# AFE.net
KiCad netlist of a schematic drawn in Altium Designer
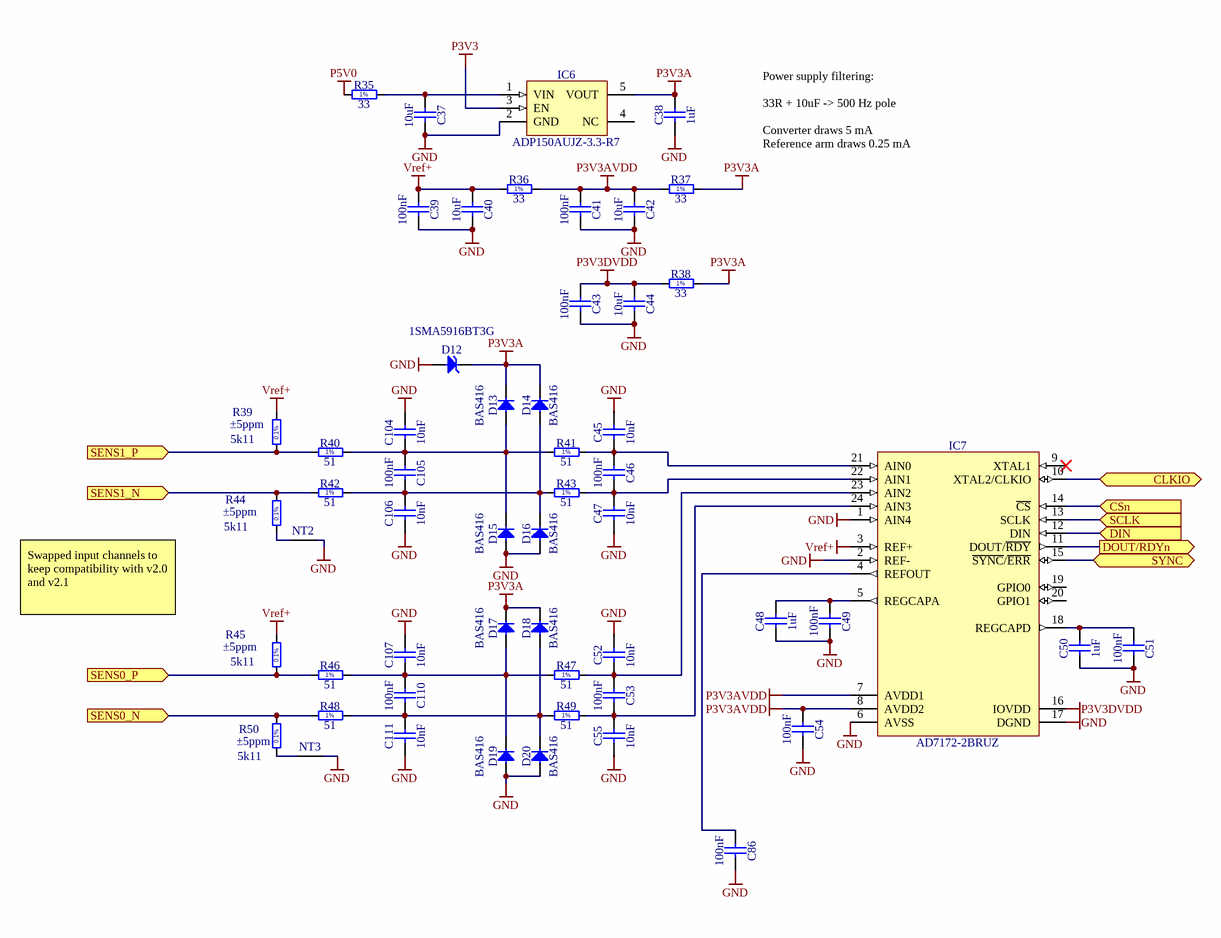
[diagram p0: AFE.SchDoc]

(export (version "E")
  (design (tool "Eeschema 10.0.6"))
  (components
    (comp (ref "C37")
      (value "10uF")
      (footprint "CAPC2012X135N")
      (description "Non-polarised capacitor")
      (fields
        (field (name "PART NUMBER") "CC0805_10UF_16V_10%_X5R")
        (field (name "VOLTAGE") "16V")
        (field (name "AUTHOR") "CERN DEM JLC")
      )
      (libsource (lib "Capacitors") (part "Capacitor - non polarized"))
    )
    (comp (ref "C38")
      (value "1uF")
      (footprint "CAPC1608X87N")
      (description "Non-polarised capacitor")
      (fields
        (field (name "PART NUMBER") "CC0603_1UF_25V_10%_X7R")
        (field (name "VOLTAGE") "25V")
        (field (name "AUTHOR") "CERN DEM JLC")
      )
      (libsource (lib "Capacitors") (part "Capacitor - non polarized"))
    )
    (comp (ref "C39")
      (value "100nF")
      (footprint "CAPC1005X55N")
      (description "Non-polarised capacitor")
      (fields
        (field (name "PART NUMBER") "CC0402_100NF_16V_10%_X5R")
        (field (name "VOLTAGE") "16V")
        (field (name "AUTHOR") "CERN DEM JLC")
      )
      (libsource (lib "Capacitors") (part "Capacitor - non polarized"))
    )
    (comp (ref "C40")
      (value "10uF")
      (footprint "CAPC2012X135N")
      (description "Non-polarised capacitor")
      (fields
        (field (name "PART NUMBER") "CC0805_10UF_16V_10%_X5R")
        (field (name "VOLTAGE") "16V")
        (field (name "AUTHOR") "CERN DEM JLC")
      )
      (libsource (lib "Capacitors") (part "Capacitor - non polarized"))
    )
    (comp (ref "C41")
      (value "100nF")
      (footprint "CAPC1005X55N")
      (description "Non-polarised capacitor")
      (fields
        (field (name "PART NUMBER") "CC0402_100NF_16V_10%_X5R")
        (field (name "VOLTAGE") "16V")
        (field (name "AUTHOR") "CERN DEM JLC")
      )
      (libsource (lib "Capacitors") (part "Capacitor - non polarized"))
    )
    (comp (ref "C42")
      (value "10uF")
      (footprint "CAPC2012X135N")
      (description "Non-polarised capacitor")
      (fields
        (field (name "PART NUMBER") "CC0805_10UF_16V_10%_X5R")
        (field (name "VOLTAGE") "16V")
        (field (name "AUTHOR") "CERN DEM JLC")
      )
      (libsource (lib "Capacitors") (part "Capacitor - non polarized"))
    )
    (comp (ref "C43")
      (value "100nF")
      (footprint "CAPC1005X55N")
      (description "Non-polarised capacitor")
      (fields
        (field (name "PART NUMBER") "CC0402_100NF_16V_10%_X5R")
        (field (name "VOLTAGE") "16V")
        (field (name "AUTHOR") "CERN DEM JLC")
      )
      (libsource (lib "Capacitors") (part "Capacitor - non polarized"))
    )
    (comp (ref "C44")
      (value "10uF")
      (footprint "CAPC2012X135N")
      (description "Non-polarised capacitor")
      (fields
        (field (name "PART NUMBER") "CC0805_10UF_16V_10%_X5R")
        (field (name "VOLTAGE") "16V")
        (field (name "AUTHOR") "CERN DEM JLC")
      )
      (libsource (lib "Capacitors") (part "Capacitor - non polarized"))
    )
    (comp (ref "C45")
      (value "10nF")
      (footprint "CAPC1005X55N")
      (description "Non-polarised capacitor")
      (fields
        (field (name "PART NUMBER") "CC0402_10NF_50V_10%_X7R")
        (field (name "VOLTAGE") "50V")
        (field (name "AUTHOR") "CERN DEM MR")
      )
      (libsource (lib "Capacitors") (part "Capacitor - non polarized"))
    )
    (comp (ref "C46")
      (value "100nF")
      (footprint "CAPC1005X55N")
      (description "Non-polarised capacitor")
      (fields
        (field (name "PART NUMBER") "CC0402_100NF_16V_10%_X5R")
        (field (name "VOLTAGE") "16V")
        (field (name "AUTHOR") "CERN DEM JLC")
      )
      (libsource (lib "Capacitors") (part "Capacitor - non polarized"))
    )
    (comp (ref "C47")
      (value "10nF")
      (footprint "CAPC1005X55N")
      (description "Non-polarised capacitor")
      (fields
        (field (name "PART NUMBER") "CC0402_10NF_50V_10%_X7R")
        (field (name "VOLTAGE") "50V")
        (field (name "AUTHOR") "CERN DEM MR")
      )
      (libsource (lib "Capacitors") (part "Capacitor - non polarized"))
    )
    (comp (ref "C48")
      (value "1uF")
      (footprint "CAPC1608X87N")
      (description "Non-polarised capacitor")
      (fields
        (field (name "PART NUMBER") "CC0603_1UF_25V_10%_X7R")
        (field (name "VOLTAGE") "25V")
        (field (name "AUTHOR") "CERN DEM JLC")
      )
      (libsource (lib "Capacitors") (part "Capacitor - non polarized"))
    )
    (comp (ref "C49")
      (value "100nF")
      (footprint "CAPC1005X55N")
      (description "Non-polarised capacitor")
      (fields
        (field (name "PART NUMBER") "CC0402_100NF_16V_10%_X5R")
        (field (name "VOLTAGE") "16V")
        (field (name "AUTHOR") "CERN DEM JLC")
      )
      (libsource (lib "Capacitors") (part "Capacitor - non polarized"))
    )
    (comp (ref "C50")
      (value "1uF")
      (footprint "CAPC1608X87N")
      (description "Non-polarised capacitor")
      (fields
        (field (name "PART NUMBER") "CC0603_1UF_25V_10%_X7R")
        (field (name "VOLTAGE") "25V")
        (field (name "AUTHOR") "CERN DEM JLC")
      )
      (libsource (lib "Capacitors") (part "Capacitor - non polarized"))
    )
    (comp (ref "C51")
      (value "100nF")
      (footprint "CAPC1005X55N")
      (description "Non-polarised capacitor")
      (fields
        (field (name "PART NUMBER") "CC0402_100NF_16V_10%_X5R")
        (field (name "VOLTAGE") "16V")
        (field (name "AUTHOR") "CERN DEM JLC")
      )
      (libsource (lib "Capacitors") (part "Capacitor - non polarized"))
    )
    (comp (ref "C52")
      (value "10nF")
      (footprint "CAPC1005X55N")
      (description "Non-polarised capacitor")
      (fields
        (field (name "PART NUMBER") "CC0402_10NF_50V_10%_X7R")
        (field (name "VOLTAGE") "50V")
        (field (name "AUTHOR") "CERN DEM MR")
      )
      (libsource (lib "Capacitors") (part "Capacitor - non polarized"))
    )
    (comp (ref "C53")
      (value "100nF")
      (footprint "CAPC1005X55N")
      (description "Non-polarised capacitor")
      (fields
        (field (name "PART NUMBER") "CC0402_100NF_16V_10%_X5R")
        (field (name "VOLTAGE") "16V")
        (field (name "AUTHOR") "CERN DEM JLC")
      )
      (libsource (lib "Capacitors") (part "Capacitor - non polarized"))
    )
    (comp (ref "C54")
      (value "100nF")
      (footprint "CAPC1005X55N")
      (description "Non-polarised capacitor")
      (fields
        (field (name "PART NUMBER") "CC0402_100NF_16V_10%_X5R")
        (field (name "VOLTAGE") "16V")
        (field (name "AUTHOR") "CERN DEM JLC")
      )
      (libsource (lib "Capacitors") (part "Capacitor - non polarized"))
    )
    (comp (ref "C55")
      (value "10nF")
      (footprint "CAPC1005X55N")
      (description "Non-polarised capacitor")
      (fields
        (field (name "PART NUMBER") "CC0402_10NF_50V_10%_X7R")
        (field (name "VOLTAGE") "50V")
        (field (name "AUTHOR") "CERN DEM MR")
      )
      (libsource (lib "Capacitors") (part "Capacitor - non polarized"))
    )
    (comp (ref "C86")
      (value "100nF")
      (footprint "CAPC1005X55N")
      (description "Non-polarised capacitor")
      (fields
        (field (name "PART NUMBER") "CC0402_100NF_16V_10%_X5R")
        (field (name "VOLTAGE") "16V")
        (field (name "AUTHOR") "CERN DEM JLC")
      )
      (libsource (lib "Capacitors") (part "Capacitor - non polarized"))
    )
    (comp (ref "C104")
      (value "10nF")
      (footprint "CAPC1005X55N")
      (description "Non-polarised capacitor")
      (fields
        (field (name "PART NUMBER") "CC0402_10NF_50V_10%_X7R")
        (field (name "VOLTAGE") "50V")
        (field (name "AUTHOR") "CERN DEM MR")
      )
      (libsource (lib "Capacitors") (part "Capacitor - non polarized"))
    )
    (comp (ref "C105")
      (value "100nF")
      (footprint "CAPC1005X55N")
      (description "Non-polarised capacitor")
      (fields
        (field (name "PART NUMBER") "CC0402_100NF_16V_10%_X5R")
        (field (name "VOLTAGE") "16V")
        (field (name "AUTHOR") "CERN DEM JLC")
      )
      (libsource (lib "Capacitors") (part "Capacitor - non polarized"))
    )
    (comp (ref "C106")
      (value "10nF")
      (footprint "CAPC1005X55N")
      (description "Non-polarised capacitor")
      (fields
        (field (name "PART NUMBER") "CC0402_10NF_50V_10%_X7R")
        (field (name "VOLTAGE") "50V")
        (field (name "AUTHOR") "CERN DEM MR")
      )
      (libsource (lib "Capacitors") (part "Capacitor - non polarized"))
    )
    (comp (ref "C107")
      (value "10nF")
      (footprint "CAPC1005X55N")
      (description "Non-polarised capacitor")
      (fields
        (field (name "PART NUMBER") "CC0402_10NF_50V_10%_X7R")
        (field (name "VOLTAGE") "50V")
        (field (name "AUTHOR") "CERN DEM MR")
      )
      (libsource (lib "Capacitors") (part "Capacitor - non polarized"))
    )
    (comp (ref "C110")
      (value "100nF")
      (footprint "CAPC1005X55N")
      (description "Non-polarised capacitor")
      (fields
        (field (name "PART NUMBER") "CC0402_100NF_16V_10%_X5R")
        (field (name "VOLTAGE") "16V")
        (field (name "AUTHOR") "CERN DEM JLC")
      )
      (libsource (lib "Capacitors") (part "Capacitor - non polarized"))
    )
    (comp (ref "C111")
      (value "10nF")
      (footprint "CAPC1005X55N")
      (description "Non-polarised capacitor")
      (fields
        (field (name "PART NUMBER") "CC0402_10NF_50V_10%_X7R")
        (field (name "VOLTAGE") "50V")
        (field (name "AUTHOR") "CERN DEM MR")
      )
      (libsource (lib "Capacitors") (part "Capacitor - non polarized"))
    )
    (comp (ref "D12")
      (value "1SMA5916BT3G")
      (footprint "DIOM5226X220N")
      (description "4.3V 1.5 Watt Plastic Surface Mount Zener Voltage Regulators")
      (fields (field (name "VOLTAGE") "4.3V") (field (name "POWER") "1.5W") (field (name "AUTHOR") "GK"))
      (libsource (lib "Diodes") (part "D_Zener_1SMA5916BT3G"))
    )
    (comp (ref "D13")
      (value "BAS416")
      (footprint "SOD2512X110N")
      (description "Diode")
      (fields
        (field (name "VOLTAGE") "75V")
        (field (name "POWER") "200mA")
        (field (name "AUTHOR") "CERN DEM JLC")
      )
      (libsource (lib "ICs And Semiconductors") (part "Diode"))
    )
    (comp (ref "D14")
      (value "BAS416")
      (footprint "SOD2512X110N")
      (description "Diode")
      (fields
        (field (name "VOLTAGE") "75V")
        (field (name "POWER") "200mA")
        (field (name "AUTHOR") "CERN DEM JLC")
      )
      (libsource (lib "ICs And Semiconductors") (part "Diode"))
    )
    (comp (ref "D15")
      (value "BAS416")
      (footprint "SOD2512X110N")
      (description "Diode")
      (fields
        (field (name "VOLTAGE") "75V")
        (field (name "POWER") "200mA")
        (field (name "AUTHOR") "CERN DEM JLC")
      )
      (libsource (lib "ICs And Semiconductors") (part "Diode"))
    )
    (comp (ref "D16")
      (value "BAS416")
      (footprint "SOD2512X110N")
      (description "Diode")
      (fields
        (field (name "VOLTAGE") "75V")
        (field (name "POWER") "200mA")
        (field (name "AUTHOR") "CERN DEM JLC")
      )
      (libsource (lib "ICs And Semiconductors") (part "Diode"))
    )
    (comp (ref "D17")
      (value "BAS416")
      (footprint "SOD2512X110N")
      (description "Diode")
      (fields
        (field (name "VOLTAGE") "75V")
        (field (name "POWER") "200mA")
        (field (name "AUTHOR") "CERN DEM JLC")
      )
      (libsource (lib "ICs And Semiconductors") (part "Diode"))
    )
    (comp (ref "D18")
      (value "BAS416")
      (footprint "SOD2512X110N")
      (description "Diode")
      (fields
        (field (name "VOLTAGE") "75V")
        (field (name "POWER") "200mA")
        (field (name "AUTHOR") "CERN DEM JLC")
      )
      (libsource (lib "ICs And Semiconductors") (part "Diode"))
    )
    (comp (ref "D19")
      (value "BAS416")
      (footprint "SOD2512X110N")
      (description "Diode")
      (fields
        (field (name "VOLTAGE") "75V")
        (field (name "POWER") "200mA")
        (field (name "AUTHOR") "CERN DEM JLC")
      )
      (libsource (lib "ICs And Semiconductors") (part "Diode"))
    )
    (comp (ref "D20")
      (value "BAS416")
      (footprint "SOD2512X110N")
      (description "Diode")
      (fields
        (field (name "VOLTAGE") "75V")
        (field (name "POWER") "200mA")
        (field (name "AUTHOR") "CERN DEM JLC")
      )
      (libsource (lib "ICs And Semiconductors") (part "Diode"))
    )
    (comp (ref "IC6")
      (value "ADP150AUJZ-3.3-R7")
      (footprint "SOT95P280X90-5N")
      (description "Ultralow Noise, 150 mA CMOS Linear Regulator")
      (fields (field (name "MANUFACTURER") "ANALOG DEVICES") (field (name "AUTHOR") "CERN DEM JLC"))
      (libsource (lib "ICs And Semiconductors") (part "ADP150AUJZ"))
    )
    (comp (ref "IC7")
      (value "AD7172-2BRUZ")
      (footprint "SOP65P640X120-24N")
      (description "32-Bit, 10 kSPS, Sigma-Delta ADC with 100 µs Settling and True Rail-to-Rail Buffers")
      (fields (field (name "MANUFACTURER") "ANALOG DEVICES") (field (name "AUTHOR") "GK"))
      (libsource (lib "LIBRARY_SCH") (part "ADC_AD7172-2"))
    )
    (comp (ref "NT2")
      (value "Net Tie")
      (footprint "Net Tie")
      (fields (field (name "AUTHOR") "CERN DEM JLC"))
      (libsource (lib "Eletro-mechanical") (part "Net Tie"))
    )
    (comp (ref "NT3")
      (value "Net Tie")
      (footprint "Net Tie")
      (fields (field (name "AUTHOR") "CERN DEM JLC"))
      (libsource (lib "Eletro-mechanical") (part "Net Tie"))
    )
    (comp (ref "R35")
      (value "33")
      (footprint "RESC1005X40N")
      (description "Resistor - 1%")
      (fields
        (field (name "PART NUMBER") "R0402_33R_1%_0.0625W_100PPM")
        (field (name "POWER") "0.0625W")
        (field (name "AUTHOR") "CERN DEM JLC")
      )
      (libsource (lib "Resistors") (part "Resistor - 1%"))
    )
    (comp (ref "R36")
      (value "33")
      (footprint "RESC1005X40N")
      (description "Resistor - 1%")
      (fields
        (field (name "PART NUMBER") "R0402_33R_1%_0.0625W_100PPM")
        (field (name "POWER") "0.0625W")
        (field (name "AUTHOR") "CERN DEM JLC")
      )
      (libsource (lib "Resistors") (part "Resistor - 1%"))
    )
    (comp (ref "R37")
      (value "33")
      (footprint "RESC1005X40N")
      (description "Resistor - 1%")
      (fields
        (field (name "PART NUMBER") "R0402_33R_1%_0.0625W_100PPM")
        (field (name "POWER") "0.0625W")
        (field (name "AUTHOR") "CERN DEM JLC")
      )
      (libsource (lib "Resistors") (part "Resistor - 1%"))
    )
    (comp (ref "R38")
      (value "33")
      (footprint "RESC1005X40N")
      (description "Resistor - 1%")
      (fields
        (field (name "PART NUMBER") "R0402_33R_1%_0.0625W_100PPM")
        (field (name "POWER") "0.0625W")
        (field (name "AUTHOR") "CERN DEM JLC")
      )
      (libsource (lib "Resistors") (part "Resistor - 1%"))
    )
    (comp (ref "R39")
      (value "5k11")
      (footprint "RESC1608X55N")
      (description "Resistor - 0.1%")
      (fields
        (field (name "PART NUMBER") "R0603_5K11_0.1%_0.063W_5PPM")
        (field (name "POWER") "0.063W")
        (field (name "TC") "±5ppm")
        (field (name "AUTHOR") "GK")
      )
      (libsource (lib "LIBRARY_SCH") (part "RES_0603_5k11_0.1%_5ppm"))
    )
    (comp (ref "R40")
      (value "51")
      (footprint "RESC1005X40N")
      (description "Resistor - 1%")
      (fields
        (field (name "PART NUMBER") "R0402_51R_1%_0.0625W_100PPM")
        (field (name "POWER") "0.0625W")
        (field (name "AUTHOR") "CERN DEM JLC")
      )
      (libsource (lib "Resistors") (part "Resistor - 1%"))
    )
    (comp (ref "R41")
      (value "51")
      (footprint "RESC1005X40N")
      (description "Resistor - 1%")
      (fields
        (field (name "PART NUMBER") "R0402_51R_1%_0.0625W_100PPM")
        (field (name "POWER") "0.0625W")
        (field (name "AUTHOR") "CERN DEM JLC")
      )
      (libsource (lib "Resistors") (part "Resistor - 1%"))
    )
    (comp (ref "R42")
      (value "51")
      (footprint "RESC1005X40N")
      (description "Resistor - 1%")
      (fields
        (field (name "PART NUMBER") "R0402_51R_1%_0.0625W_100PPM")
        (field (name "POWER") "0.0625W")
        (field (name "AUTHOR") "CERN DEM JLC")
      )
      (libsource (lib "Resistors") (part "Resistor - 1%"))
    )
    (comp (ref "R43")
      (value "51")
      (footprint "RESC1005X40N")
      (description "Resistor - 1%")
      (fields
        (field (name "PART NUMBER") "R0402_51R_1%_0.0625W_100PPM")
        (field (name "POWER") "0.0625W")
        (field (name "AUTHOR") "CERN DEM JLC")
      )
      (libsource (lib "Resistors") (part "Resistor - 1%"))
    )
    (comp (ref "R44")
      (value "5k11")
      (footprint "RESC1608X55N")
      (description "Resistor - 0.1%")
      (fields
        (field (name "PART NUMBER") "R0603_5K11_0.1%_0.063W_5PPM")
        (field (name "POWER") "0.063W")
        (field (name "TC") "±5ppm")
        (field (name "AUTHOR") "GK")
      )
      (libsource (lib "LIBRARY_SCH") (part "RES_0603_5k11_0.1%_5ppm"))
    )
    (comp (ref "R45")
      (value "5k11")
      (footprint "RESC1608X55N")
      (description "Resistor - 0.1%")
      (fields
        (field (name "PART NUMBER") "R0603_5K11_0.1%_0.063W_5PPM")
        (field (name "POWER") "0.063W")
        (field (name "TC") "±5ppm")
        (field (name "AUTHOR") "GK")
      )
      (libsource (lib "LIBRARY_SCH") (part "RES_0603_5k11_0.1%_5ppm"))
    )
    (comp (ref "R46")
      (value "51")
      (footprint "RESC1005X40N")
      (description "Resistor - 1%")
      (fields
        (field (name "PART NUMBER") "R0402_51R_1%_0.0625W_100PPM")
        (field (name "POWER") "0.0625W")
        (field (name "AUTHOR") "CERN DEM JLC")
      )
      (libsource (lib "Resistors") (part "Resistor - 1%"))
    )
    (comp (ref "R47")
      (value "51")
      (footprint "RESC1005X40N")
      (description "Resistor - 1%")
      (fields
        (field (name "PART NUMBER") "R0402_51R_1%_0.0625W_100PPM")
        (field (name "POWER") "0.0625W")
        (field (name "AUTHOR") "CERN DEM JLC")
      )
      (libsource (lib "Resistors") (part "Resistor - 1%"))
    )
    (comp (ref "R48")
      (value "51")
      (footprint "RESC1005X40N")
      (description "Resistor - 1%")
      (fields
        (field (name "PART NUMBER") "R0402_51R_1%_0.0625W_100PPM")
        (field (name "POWER") "0.0625W")
        (field (name "AUTHOR") "CERN DEM JLC")
      )
      (libsource (lib "Resistors") (part "Resistor - 1%"))
    )
    (comp (ref "R49")
      (value "51")
      (footprint "RESC1005X40N")
      (description "Resistor - 1%")
      (fields
        (field (name "PART NUMBER") "R0402_51R_1%_0.0625W_100PPM")
        (field (name "POWER") "0.0625W")
        (field (name "AUTHOR") "CERN DEM JLC")
      )
      (libsource (lib "Resistors") (part "Resistor - 1%"))
    )
    (comp (ref "R50")
      (value "5k11")
      (footprint "RESC1608X55N")
      (description "Resistor - 0.1%")
      (fields
        (field (name "PART NUMBER") "R0603_5K11_0.1%_0.063W_5PPM")
        (field (name "POWER") "0.063W")
        (field (name "TC") "±5ppm")
        (field (name "AUTHOR") "GK")
      )
      (libsource (lib "LIBRARY_SCH") (part "RES_0603_5k11_0.1%_5ppm"))
    )
  )
  (nets
    (net (code "1") (name "/CLKIO") (class "Default")
      (node (ref "IC7") (pin "10") (pinfunction "XTAL2/CLKIO_10") (pintype "bidirectional"))
    )
    (net (code "2") (name "/CSn") (class "Default")
      (node (ref "IC7") (pin "14") (pinfunction "~{CS}_14") (pintype "input"))
    )
    (net (code "3") (name "/DIN") (class "Default")
      (node (ref "IC7") (pin "12") (pinfunction "DIN_12") (pintype "input"))
    )
    (net (code "4") (name "/DOUT{slash}RDYn") (class "Default")
      (node (ref "IC7") (pin "11") (pinfunction "DOUT/~{RDY}_11") (pintype "output"))
    )
    (net (code "5") (name "/SCLK") (class "Default")
      (node (ref "IC7") (pin "13") (pinfunction "SCLK_13") (pintype "input"))
    )
    (net (code "6") (name "/SENS0_N") (class "Default")
      (node (ref "R48") (pin "1") (pinfunction "1_1") (pintype "passive"))
      (node (ref "R50") (pin "2") (pinfunction "2_2") (pintype "passive"))
    )
    (net (code "7") (name "/SENS0_P") (class "Default")
      (node (ref "R45") (pin "1") (pinfunction "1_1") (pintype "passive"))
      (node (ref "R46") (pin "1") (pinfunction "1_1") (pintype "passive"))
    )
    (net (code "8") (name "/SENS1_N") (class "Default")
      (node (ref "R42") (pin "1") (pinfunction "1_1") (pintype "passive"))
      (node (ref "R44") (pin "2") (pinfunction "2_2") (pintype "passive"))
    )
    (net (code "9") (name "/SENS1_P") (class "Default")
      (node (ref "R39") (pin "1") (pinfunction "1_1") (pintype "passive"))
      (node (ref "R40") (pin "1") (pinfunction "1_1") (pintype "passive"))
    )
    (net (code "10") (name "/SYNC") (class "Default")
      (node (ref "IC7") (pin "15") (pinfunction "~{SYNC}/~{ERR}_15") (pintype "bidirectional"))
    )
    (net (code "11") (name "GND") (class "Default")
      (node (ref "C104") (pin "2") (pinfunction "2_2") (pintype "passive"))
      (node (ref "C106") (pin "1") (pinfunction "1_1") (pintype "passive"))
      (node (ref "C107") (pin "2") (pinfunction "2_2") (pintype "passive"))
      (node (ref "C111") (pin "1") (pinfunction "1_1") (pintype "passive"))
      (node (ref "C37") (pin "2") (pinfunction "2_2") (pintype "passive"))
      (node (ref "C38") (pin "1") (pinfunction "1_1") (pintype "passive"))
      (node (ref "C39") (pin "2") (pinfunction "2_2") (pintype "passive"))
      (node (ref "C40") (pin "2") (pinfunction "2_2") (pintype "passive"))
      (node (ref "C41") (pin "2") (pinfunction "2_2") (pintype "passive"))
      (node (ref "C42") (pin "2") (pinfunction "2_2") (pintype "passive"))
      (node (ref "C43") (pin "2") (pinfunction "2_2") (pintype "passive"))
      (node (ref "C44") (pin "2") (pinfunction "2_2") (pintype "passive"))
      (node (ref "C45") (pin "2") (pinfunction "2_2") (pintype "passive"))
      (node (ref "C47") (pin "1") (pinfunction "1_1") (pintype "passive"))
      (node (ref "C48") (pin "1") (pinfunction "1_1") (pintype "passive"))
      (node (ref "C49") (pin "2") (pinfunction "2_2") (pintype "passive"))
      (node (ref "C50") (pin "1") (pinfunction "1_1") (pintype "passive"))
      (node (ref "C51") (pin "2") (pinfunction "2_2") (pintype "passive"))
      (node (ref "C52") (pin "2") (pinfunction "2_2") (pintype "passive"))
      (node (ref "C54") (pin "2") (pinfunction "2_2") (pintype "passive"))
      (node (ref "C55") (pin "1") (pinfunction "1_1") (pintype "passive"))
      (node (ref "C86") (pin "2") (pinfunction "2_2") (pintype "passive"))
      (node (ref "D12") (pin "2") (pinfunction "A_2") (pintype "passive"))
      (node (ref "D15") (pin "2") (pinfunction "A_2") (pintype "passive"))
      (node (ref "D16") (pin "2") (pinfunction "A_2") (pintype "passive"))
      (node (ref "D19") (pin "2") (pinfunction "A_2") (pintype "passive"))
      (node (ref "D20") (pin "2") (pinfunction "A_2") (pintype "passive"))
      (node (ref "IC6") (pin "2") (pinfunction "GND_2") (pintype "power_in"))
      (node (ref "IC7") (pin "1") (pinfunction "AIN4_1") (pintype "input"))
      (node (ref "IC7") (pin "17") (pinfunction "DGND_17") (pintype "power_in"))
      (node (ref "IC7") (pin "2") (pinfunction "REF-_2") (pintype "input"))
      (node (ref "IC7") (pin "6") (pinfunction "AVSS_6") (pintype "power_in"))
      (node (ref "NT2") (pin "2") (pinfunction "2_2") (pintype "bidirectional"))
      (node (ref "NT3") (pin "2") (pinfunction "2_2") (pintype "bidirectional"))
    )
    (net (code "12") (name "Net-(D13-A)") (class "Default")
      (node (ref "C104") (pin "1") (pinfunction "1_1") (pintype "passive"))
      (node (ref "C105") (pin "1") (pinfunction "1_1") (pintype "passive"))
      (node (ref "D13") (pin "2") (pinfunction "A_2") (pintype "passive"))
      (node (ref "D15") (pin "1") (pinfunction "C_1") (pintype "passive"))
      (node (ref "R40") (pin "2") (pinfunction "2_2") (pintype "passive"))
      (node (ref "R41") (pin "1") (pinfunction "1_1") (pintype "passive"))
    )
    (net (code "13") (name "Net-(D14-A)") (class "Default")
      (node (ref "C105") (pin "2") (pinfunction "2_2") (pintype "passive"))
      (node (ref "C106") (pin "2") (pinfunction "2_2") (pintype "passive"))
      (node (ref "D14") (pin "2") (pinfunction "A_2") (pintype "passive"))
      (node (ref "D16") (pin "1") (pinfunction "C_1") (pintype "passive"))
      (node (ref "R42") (pin "2") (pinfunction "2_2") (pintype "passive"))
      (node (ref "R43") (pin "1") (pinfunction "1_1") (pintype "passive"))
    )
    (net (code "14") (name "Net-(D17-A)") (class "Default")
      (node (ref "C107") (pin "1") (pinfunction "1_1") (pintype "passive"))
      (node (ref "C110") (pin "1") (pinfunction "1_1") (pintype "passive"))
      (node (ref "D17") (pin "2") (pinfunction "A_2") (pintype "passive"))
      (node (ref "D19") (pin "1") (pinfunction "C_1") (pintype "passive"))
      (node (ref "R46") (pin "2") (pinfunction "2_2") (pintype "passive"))
      (node (ref "R47") (pin "1") (pinfunction "1_1") (pintype "passive"))
    )
    (net (code "15") (name "Net-(D18-A)") (class "Default")
      (node (ref "C110") (pin "2") (pinfunction "2_2") (pintype "passive"))
      (node (ref "C111") (pin "2") (pinfunction "2_2") (pintype "passive"))
      (node (ref "D18") (pin "2") (pinfunction "A_2") (pintype "passive"))
      (node (ref "D20") (pin "1") (pinfunction "C_1") (pintype "passive"))
      (node (ref "R48") (pin "2") (pinfunction "2_2") (pintype "passive"))
      (node (ref "R49") (pin "1") (pinfunction "1_1") (pintype "passive"))
    )
    (net (code "16") (name "Net-(IC6-VIN)") (class "Default")
      (node (ref "C37") (pin "1") (pinfunction "1_1") (pintype "passive"))
      (node (ref "IC6") (pin "1") (pinfunction "VIN_1") (pintype "input"))
      (node (ref "R35") (pin "2") (pinfunction "2_2") (pintype "passive"))
    )
    (net (code "17") (name "Net-(IC7-AIN0)") (class "Default")
      (node (ref "C45") (pin "1") (pinfunction "1_1") (pintype "passive"))
      (node (ref "C46") (pin "1") (pinfunction "1_1") (pintype "passive"))
      (node (ref "IC7") (pin "21") (pinfunction "AIN0_21") (pintype "input"))
      (node (ref "R41") (pin "2") (pinfunction "2_2") (pintype "passive"))
    )
    (net (code "18") (name "Net-(IC7-AIN1)") (class "Default")
      (node (ref "C46") (pin "2") (pinfunction "2_2") (pintype "passive"))
      (node (ref "C47") (pin "2") (pinfunction "2_2") (pintype "passive"))
      (node (ref "IC7") (pin "22") (pinfunction "AIN1_22") (pintype "input"))
      (node (ref "R43") (pin "2") (pinfunction "2_2") (pintype "passive"))
    )
    (net (code "19") (name "Net-(IC7-AIN2)") (class "Default")
      (node (ref "C52") (pin "1") (pinfunction "1_1") (pintype "passive"))
      (node (ref "C53") (pin "1") (pinfunction "1_1") (pintype "passive"))
      (node (ref "IC7") (pin "23") (pinfunction "AIN2_23") (pintype "input"))
      (node (ref "R47") (pin "2") (pinfunction "2_2") (pintype "passive"))
    )
    (net (code "20") (name "Net-(IC7-AIN3)") (class "Default")
      (node (ref "C53") (pin "2") (pinfunction "2_2") (pintype "passive"))
      (node (ref "C55") (pin "2") (pinfunction "2_2") (pintype "passive"))
      (node (ref "IC7") (pin "24") (pinfunction "AIN3_24") (pintype "input"))
      (node (ref "R49") (pin "2") (pinfunction "2_2") (pintype "passive"))
    )
    (net (code "21") (name "Net-(IC7-REFOUT)") (class "Default")
      (node (ref "C86") (pin "1") (pinfunction "1_1") (pintype "passive"))
      (node (ref "IC7") (pin "4") (pinfunction "REFOUT_4") (pintype "output"))
    )
    (net (code "22") (name "Net-(IC7-REGCAPA)") (class "Default")
      (node (ref "C48") (pin "2") (pinfunction "2_2") (pintype "passive"))
      (node (ref "C49") (pin "1") (pinfunction "1_1") (pintype "passive"))
      (node (ref "IC7") (pin "5") (pinfunction "REGCAPA_5") (pintype "output"))
    )
    (net (code "23") (name "Net-(IC7-REGCAPD)") (class "Default")
      (node (ref "C50") (pin "2") (pinfunction "2_2") (pintype "passive"))
      (node (ref "C51") (pin "1") (pinfunction "1_1") (pintype "passive"))
      (node (ref "IC7") (pin "18") (pinfunction "REGCAPD_18") (pintype "output"))
    )
    (net (code "24") (name "Net-(NT2-Pad1)") (class "Default")
      (node (ref "NT2") (pin "1") (pinfunction "1_1") (pintype "bidirectional"))
      (node (ref "R44") (pin "1") (pinfunction "1_1") (pintype "passive"))
    )
    (net (code "25") (name "Net-(NT3-Pad1)") (class "Default")
      (node (ref "NT3") (pin "1") (pinfunction "1_1") (pintype "bidirectional"))
      (node (ref "R50") (pin "1") (pinfunction "1_1") (pintype "passive"))
    )
    (net (code "26") (name "P3V3") (class "Default")
      (node (ref "IC6") (pin "3") (pinfunction "EN_3") (pintype "input"))
    )
    (net (code "27") (name "P3V3A") (class "Default")
      (node (ref "C38") (pin "2") (pinfunction "2_2") (pintype "passive"))
      (node (ref "D12") (pin "1") (pinfunction "C_1") (pintype "passive"))
      (node (ref "D13") (pin "1") (pinfunction "C_1") (pintype "passive"))
      (node (ref "D14") (pin "1") (pinfunction "C_1") (pintype "passive"))
      (node (ref "D17") (pin "1") (pinfunction "C_1") (pintype "passive"))
      (node (ref "D18") (pin "1") (pinfunction "C_1") (pintype "passive"))
      (node (ref "IC6") (pin "5") (pinfunction "VOUT_5") (pintype "power_in"))
      (node (ref "R37") (pin "2") (pinfunction "2_2") (pintype "passive"))
      (node (ref "R38") (pin "2") (pinfunction "2_2") (pintype "passive"))
    )
    (net (code "28") (name "P3V3AVDD") (class "Default")
      (node (ref "C41") (pin "1") (pinfunction "1_1") (pintype "passive"))
      (node (ref "C42") (pin "1") (pinfunction "1_1") (pintype "passive"))
      (node (ref "C54") (pin "1") (pinfunction "1_1") (pintype "passive"))
      (node (ref "IC7") (pin "7") (pinfunction "AVDD1_7") (pintype "power_in"))
      (node (ref "IC7") (pin "8") (pinfunction "AVDD2_8") (pintype "power_in"))
      (node (ref "R36") (pin "2") (pinfunction "2_2") (pintype "passive"))
      (node (ref "R37") (pin "1") (pinfunction "1_1") (pintype "passive"))
    )
    (net (code "29") (name "P3V3DVDD") (class "Default")
      (node (ref "C43") (pin "1") (pinfunction "1_1") (pintype "passive"))
      (node (ref "C44") (pin "1") (pinfunction "1_1") (pintype "passive"))
      (node (ref "IC7") (pin "16") (pinfunction "IOVDD_16") (pintype "power_in"))
      (node (ref "R38") (pin "1") (pinfunction "1_1") (pintype "passive"))
    )
    (net (code "30") (name "P5V0") (class "Default")
      (node (ref "R35") (pin "1") (pinfunction "1_1") (pintype "passive"))
    )
    (net (code "31") (name "Vref+") (class "Default")
      (node (ref "C39") (pin "1") (pinfunction "1_1") (pintype "passive"))
      (node (ref "C40") (pin "1") (pinfunction "1_1") (pintype "passive"))
      (node (ref "IC7") (pin "3") (pinfunction "REF+_3") (pintype "input"))
      (node (ref "R36") (pin "1") (pinfunction "1_1") (pintype "passive"))
      (node (ref "R39") (pin "2") (pinfunction "2_2") (pintype "passive"))
      (node (ref "R45") (pin "2") (pinfunction "2_2") (pintype "passive"))
    )
    (net (code "32") (name "unconnected-(IC6-NC-Pad4)") (class "Default")
      (node (ref "IC6") (pin "4") (pinfunction "NC_4") (pintype "passive"))
    )
    (net (code "33") (name "unconnected-(IC7-GPIO0-Pad19)") (class "Default")
      (node (ref "IC7") (pin "19") (pinfunction "GPIO0_19") (pintype "bidirectional"))
    )
    (net (code "34") (name "unconnected-(IC7-GPIO1-Pad20)") (class "Default")
      (node (ref "IC7") (pin "20") (pinfunction "GPIO1_20") (pintype "bidirectional"))
    )
    (net (code "35") (name "unconnected-(IC7-XTAL1-Pad9)") (class "Default")
      (node (ref "IC7") (pin "9") (pinfunction "XTAL1_9") (pintype "input+no_connect"))
    )
  )
)
